# keypad.net
KiCad netlist of a schematic drawn in EAGLE
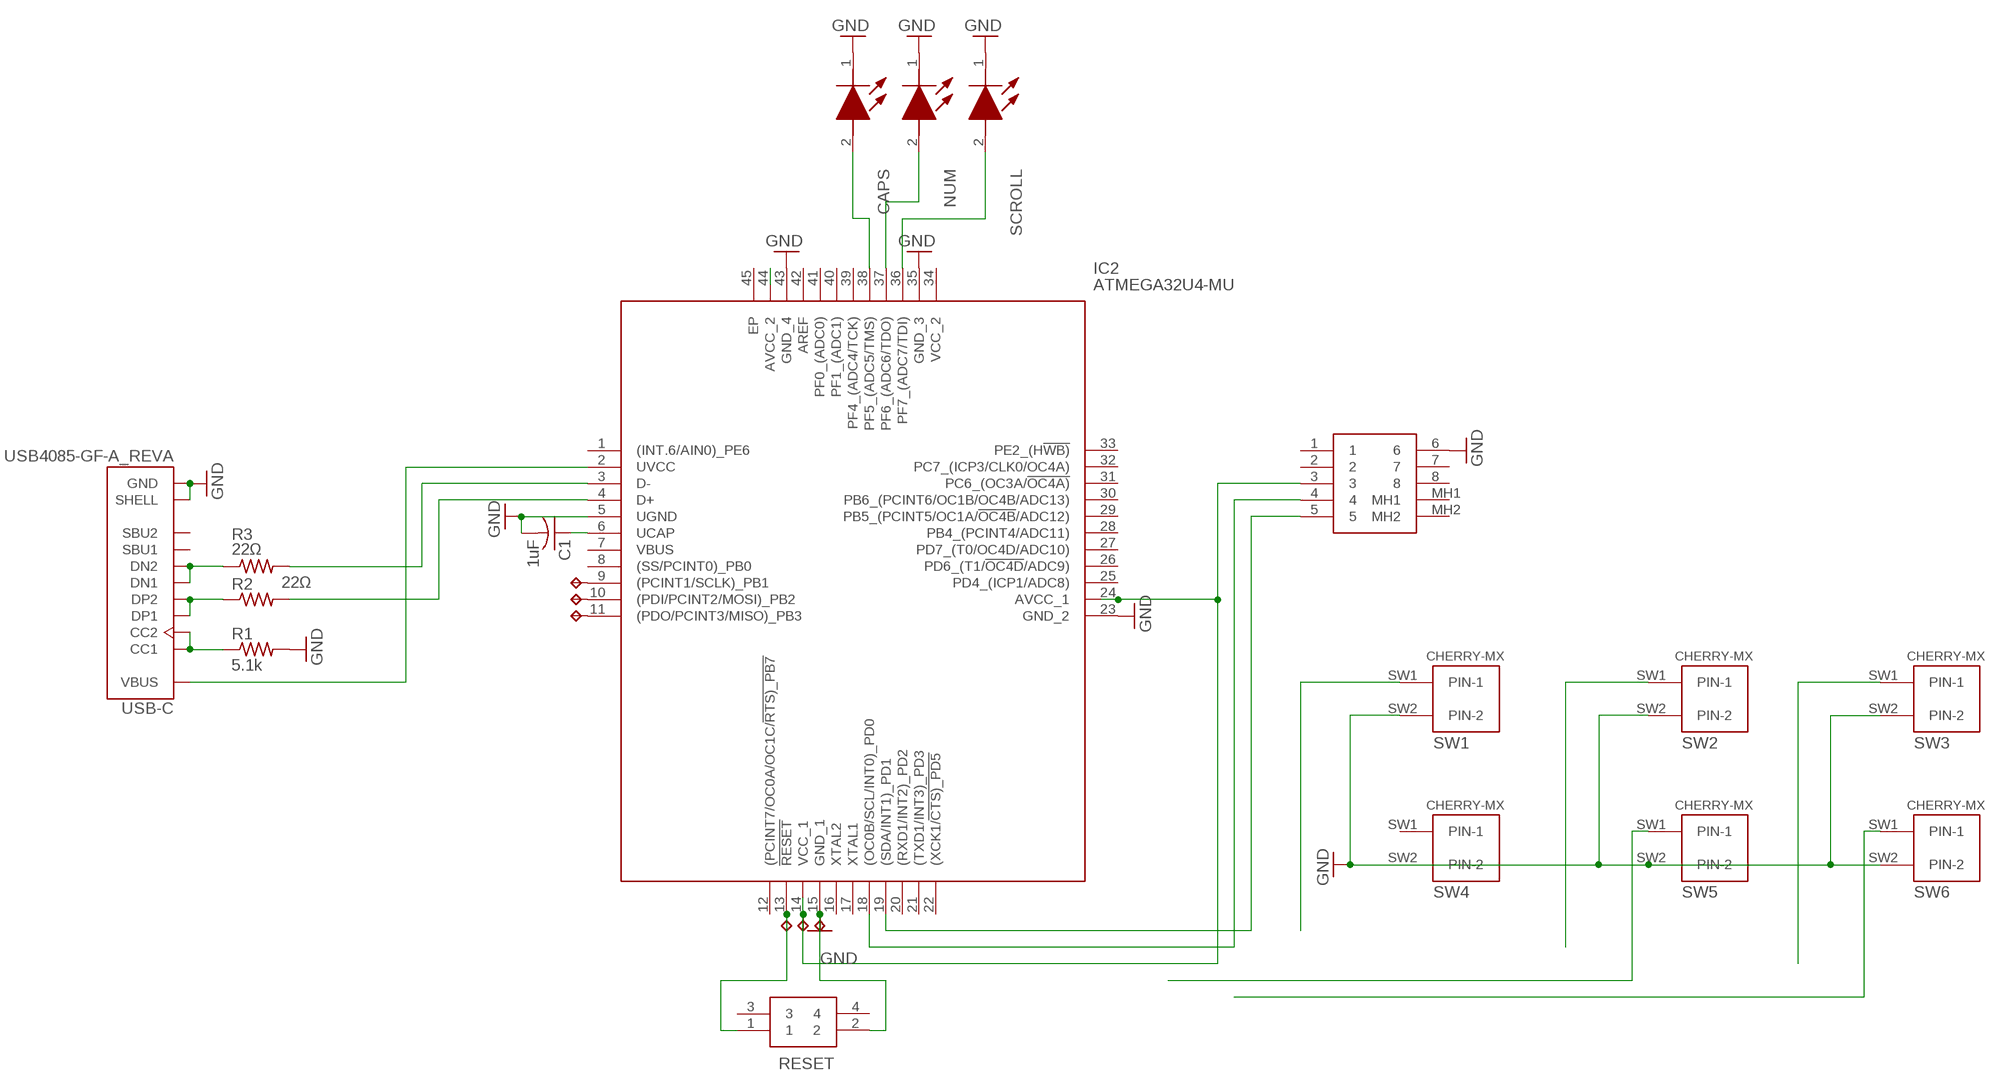
[diagram p0: schematic, sheet 1]

(export (version "E")
  (design (tool "Eeschema 10.0.6"))
  (components
    (comp (ref "5V")
      (value "TPTP17R")
      (footprint "eagle-import:TP17R")
      (libsource (lib "eagle-import") (part "TPTP17R"))
    )
    (comp (ref "C1")
      (value "1uF")
      (footprint "eagle-import:C0805")
      (libsource (lib "eagle-import") (part "C-USC0805"))
    )
    (comp (ref "CAPS")
      (value "155060GS75300")
      (footprint "eagle-import:155060GS75300")
      (fields (field (name "MOUSER_PART_NUMBER") "710-155060GS75300"))
      (libsource (lib "eagle-import") (part "155060GS75300"))
    )
    (comp (ref "GND")
      (value "TPTP17R")
      (footprint "eagle-import:TP17R")
      (libsource (lib "eagle-import") (part "TPTP17R"))
    )
    (comp (ref "IC2")
      (value "ATMEGA32U4-MU")
      (footprint "eagle-import:QFN50P700X700X100-45N")
      (fields (field (name "MOUSER_PART_NUMBER") "556-ATMEGA32U4-MU"))
      (libsource (lib "eagle-import") (part "ATMEGA32U4-MU"))
    )
    (comp (ref "J2")
      (value "SS-60300-046")
      (footprint "eagle-import:SS60300046")
      (fields (field (name "MOUSER_PART_NUMBER") "530-SS-60300-046"))
      (libsource (lib "eagle-import") (part "SS-60300-046"))
    )
    (comp (ref "MISO")
      (value "TPTP17R")
      (footprint "eagle-import:TP17R")
      (libsource (lib "eagle-import") (part "TPTP17R"))
    )
    (comp (ref "MOSI")
      (value "TPTP17R")
      (footprint "eagle-import:TP17R")
      (libsource (lib "eagle-import") (part "TPTP17R"))
    )
    (comp (ref "NUM")
      (value "155060GS75300")
      (footprint "eagle-import:155060GS75300")
      (fields (field (name "MOUSER_PART_NUMBER") "710-155060GS75300"))
      (libsource (lib "eagle-import") (part "155060GS75300"))
    )
    (comp (ref "R1")
      (value "5.1k")
      (footprint "eagle-import:R0603")
      (libsource (lib "eagle-import") (part "R-US_R0603"))
    )
    (comp (ref "R2")
      (value "22Ω")
      (footprint "eagle-import:R0805")
      (libsource (lib "eagle-import") (part "R-US_R0805"))
    )
    (comp (ref "R3")
      (value "22Ω")
      (footprint "eagle-import:R0805")
      (libsource (lib "eagle-import") (part "R-US_R0805"))
    )
    (comp (ref "RESET")
      (value "LL3303F065QG")
      (footprint "eagle-import:LL3303F065QG")
      (fields (field (name "MOUSER_PART_NUMBER") "612-LL3303F065QG"))
      (libsource (lib "eagle-import") (part "LL3303F065QG"))
    )
    (comp (ref "RST")
      (value "TPTP17R")
      (footprint "eagle-import:TP17R")
      (libsource (lib "eagle-import") (part "TPTP17R"))
    )
    (comp (ref "SCLK")
      (value "TPTP17R")
      (footprint "eagle-import:TP17R")
      (libsource (lib "eagle-import") (part "TPTP17R"))
    )
    (comp (ref "SCROLL")
      (value "155060GS75300")
      (footprint "eagle-import:155060GS75300")
      (fields (field (name "MOUSER_PART_NUMBER") "710-155060GS75300"))
      (libsource (lib "eagle-import") (part "155060GS75300"))
    )
    (comp (ref "SW1")
      (value "CHERRY-MX")
      (footprint "eagle-import:CHERRY-MX")
      (libsource (lib "eagle-import") (part "CHERRY-MX"))
    )
    (comp (ref "SW2")
      (value "CHERRY-MX")
      (footprint "eagle-import:CHERRY-MX")
      (libsource (lib "eagle-import") (part "CHERRY-MX"))
    )
    (comp (ref "SW3")
      (value "CHERRY-MX")
      (footprint "eagle-import:CHERRY-MX")
      (libsource (lib "eagle-import") (part "CHERRY-MX"))
    )
    (comp (ref "SW4")
      (value "CHERRY-MX")
      (footprint "eagle-import:CHERRY-MX")
      (libsource (lib "eagle-import") (part "CHERRY-MX"))
    )
    (comp (ref "SW5")
      (value "CHERRY-MX")
      (footprint "eagle-import:CHERRY-MX")
      (libsource (lib "eagle-import") (part "CHERRY-MX"))
    )
    (comp (ref "SW6")
      (value "CHERRY-MX")
      (footprint "eagle-import:CHERRY-MX")
      (libsource (lib "eagle-import") (part "CHERRY-MX"))
    )
    (comp (ref "USB-C")
      (value "USB4085-GF-A_REVA")
      (footprint "eagle-import:GCT_USB4085-GF-A_REVA")
      (fields (field (name "MF") "Global Connector Technology") (field (name "MP") "USB4085-GF-A"))
      (libsource (lib "eagle-import") (part "USB4085-GF-A_REVA"))
    )
  )
  (nets
    (net (code "1") (name "/VCC") (class "Default")
      (node (ref "5V") (pin "TP") (pinfunction "TP_TP") (pintype "input"))
      (node (ref "IC2") (pin "14") (pinfunction "VCC_1_14") (pintype "bidirectional"))
      (node (ref "IC2") (pin "24") (pinfunction "AVCC_1_24") (pintype "bidirectional"))
      (node (ref "IC2") (pin "44") (pinfunction "AVCC_2_44") (pintype "bidirectional"))
      (node (ref "J2") (pin "3") (pinfunction "3_3") (pintype "bidirectional"))
    )
    (net (code "2") (name "GND") (class "Default")
      (node (ref "C1") (pin "2") (pinfunction "2_2") (pintype "passive"))
      (node (ref "CAPS") (pin "1") (pinfunction "K_1") (pintype "bidirectional"))
      (node (ref "GND") (pin "TP") (pinfunction "TP_TP") (pintype "input"))
      (node (ref "IC2") (pin "15") (pinfunction "GND_1_15") (pintype "bidirectional"))
      (node (ref "IC2") (pin "23") (pinfunction "GND_2_23") (pintype "bidirectional"))
      (node (ref "IC2") (pin "35") (pinfunction "GND_3_35") (pintype "bidirectional"))
      (node (ref "IC2") (pin "43") (pinfunction "GND_4_43") (pintype "bidirectional"))
      (node (ref "IC2") (pin "5") (pinfunction "UGND_5") (pintype "bidirectional"))
      (node (ref "J2") (pin "6") (pinfunction "6_6") (pintype "bidirectional"))
      (node (ref "NUM") (pin "1") (pinfunction "K_1") (pintype "bidirectional"))
      (node (ref "R1") (pin "2") (pinfunction "2_2") (pintype "passive"))
      (node (ref "RESET") (pin "2") (pinfunction "2_2") (pintype "bidirectional"))
      (node (ref "SCROLL") (pin "1") (pinfunction "K_1") (pintype "bidirectional"))
      (node (ref "SW1") (pin "SW2") (pinfunction "PIN-2_SW2") (pintype "bidirectional"))
      (node (ref "SW2") (pin "SW2") (pinfunction "PIN-2_SW2") (pintype "bidirectional"))
      (node (ref "SW3") (pin "SW2") (pinfunction "PIN-2_SW2") (pintype "bidirectional"))
      (node (ref "SW4") (pin "SW2") (pinfunction "PIN-2_SW2") (pintype "bidirectional"))
      (node (ref "SW5") (pin "SW2") (pinfunction "PIN-2_SW2") (pintype "bidirectional"))
      (node (ref "SW6") (pin "SW2") (pinfunction "PIN-2_SW2") (pintype "bidirectional"))
      (node (ref "USB-C") (pin "A1") (pinfunction "GND_A1") (pintype "passive"))
      (node (ref "USB-C") (pin "A12") (pinfunction "GND_A12") (pintype "passive"))
      (node (ref "USB-C") (pin "B1") (pinfunction "GND_B1") (pintype "passive"))
      (node (ref "USB-C") (pin "B12") (pinfunction "GND_B12") (pintype "passive"))
      (node (ref "USB-C") (pin "P1") (pinfunction "SHELL_P1") (pintype "passive"))
      (node (ref "USB-C") (pin "P2") (pinfunction "SHELL_P2") (pintype "passive"))
      (node (ref "USB-C") (pin "P3") (pinfunction "SHELL_P3") (pintype "passive"))
      (node (ref "USB-C") (pin "P4") (pinfunction "SHELL_P4") (pintype "passive"))
    )
    (net (code "3") (name "Net-(CAPS-A)") (class "Default")
      (node (ref "CAPS") (pin "2") (pinfunction "A_2") (pintype "bidirectional"))
      (node (ref "IC2") (pin "38") (pinfunction "PF5_(ADC5/TMS)_38") (pintype "bidirectional"))
    )
    (net (code "4") (name "Net-(IC2-(OC0B{slash}SCL{slash}INT0)_PD0)") (class "Default")
      (node (ref "IC2") (pin "18") (pinfunction "(OC0B/SCL/INT0)_PD0_18") (pintype "bidirectional"))
      (node (ref "J2") (pin "4") (pinfunction "4_4") (pintype "bidirectional"))
    )
    (net (code "5") (name "Net-(IC2-(PCINT1{slash}SCLK)_PB1)") (class "Default")
      (node (ref "IC2") (pin "9") (pinfunction "(PCINT1/SCLK)_PB1_9") (pintype "bidirectional"))
      (node (ref "SCLK") (pin "TP") (pinfunction "TP_TP") (pintype "input"))
    )
    (net (code "6") (name "Net-(IC2-(PDI{slash}PCINT2{slash}MOSI)_PB2)") (class "Default")
      (node (ref "IC2") (pin "10") (pinfunction "(PDI/PCINT2/MOSI)_PB2_10") (pintype "bidirectional"))
      (node (ref "MOSI") (pin "TP") (pinfunction "TP_TP") (pintype "input"))
    )
    (net (code "7") (name "Net-(IC2-(PDO{slash}PCINT3{slash}MISO)_PB3)") (class "Default")
      (node (ref "IC2") (pin "11") (pinfunction "(PDO/PCINT3/MISO)_PB3_11") (pintype "bidirectional"))
      (node (ref "MISO") (pin "TP") (pinfunction "TP_TP") (pintype "input"))
    )
    (net (code "8") (name "Net-(IC2-(SDA{slash}INT1)_PD1)") (class "Default")
      (node (ref "IC2") (pin "19") (pinfunction "(SDA/INT1)_PD1_19") (pintype "bidirectional"))
      (node (ref "J2") (pin "5") (pinfunction "5_5") (pintype "bidirectional"))
    )
    (net (code "9") (name "Net-(IC2-D+)") (class "Default")
      (node (ref "IC2") (pin "4") (pinfunction "D+_4") (pintype "bidirectional"))
      (node (ref "R2") (pin "2") (pinfunction "2_2") (pintype "passive"))
    )
    (net (code "10") (name "Net-(IC2-D-)") (class "Default")
      (node (ref "IC2") (pin "3") (pinfunction "D-_3") (pintype "bidirectional"))
      (node (ref "R3") (pin "2") (pinfunction "2_2") (pintype "passive"))
    )
    (net (code "11") (name "Net-(IC2-PF6_(ADC6{slash}TDO))") (class "Default")
      (node (ref "IC2") (pin "37") (pinfunction "PF6_(ADC6/TDO)_37") (pintype "bidirectional"))
      (node (ref "NUM") (pin "2") (pinfunction "A_2") (pintype "bidirectional"))
    )
    (net (code "12") (name "Net-(IC2-PF7_(ADC7{slash}TDI))") (class "Default")
      (node (ref "IC2") (pin "36") (pinfunction "PF7_(ADC7/TDI)_36") (pintype "bidirectional"))
      (node (ref "SCROLL") (pin "2") (pinfunction "A_2") (pintype "bidirectional"))
    )
    (net (code "13") (name "Net-(IC2-UCAP)") (class "Default")
      (node (ref "C1") (pin "1") (pinfunction "1_1") (pintype "passive"))
      (node (ref "IC2") (pin "6") (pinfunction "UCAP_6") (pintype "bidirectional"))
    )
    (net (code "14") (name "Net-(IC2-UVCC)") (class "Default")
      (node (ref "IC2") (pin "2") (pinfunction "UVCC_2") (pintype "bidirectional"))
      (node (ref "USB-C") (pin "A4") (pinfunction "VBUS_A4") (pintype "power_in"))
      (node (ref "USB-C") (pin "A9") (pinfunction "VBUS_A9") (pintype "power_in"))
      (node (ref "USB-C") (pin "B4") (pinfunction "VBUS_B4") (pintype "power_in"))
      (node (ref "USB-C") (pin "B9") (pinfunction "VBUS_B9") (pintype "power_in"))
    )
    (net (code "15") (name "Net-(IC2-~{RESET})") (class "Default")
      (node (ref "IC2") (pin "13") (pinfunction "~{RESET}_13") (pintype "bidirectional"))
      (node (ref "RESET") (pin "1") (pinfunction "1_1") (pintype "bidirectional"))
      (node (ref "RST") (pin "TP") (pinfunction "TP_TP") (pintype "input"))
    )
    (net (code "16") (name "Net-(USB-C-CC1)") (class "Default")
      (node (ref "R1") (pin "1") (pinfunction "1_1") (pintype "passive"))
      (node (ref "USB-C") (pin "A5") (pinfunction "CC1_A5") (pintype "bidirectional"))
      (node (ref "USB-C") (pin "B5") (pinfunction "CC2_B5") (pintype "bidirectional"))
    )
    (net (code "17") (name "Net-(USB-C-DN1)") (class "Default")
      (node (ref "R3") (pin "1") (pinfunction "1_1") (pintype "passive"))
      (node (ref "USB-C") (pin "A7") (pinfunction "DN1_A7") (pintype "bidirectional"))
      (node (ref "USB-C") (pin "B7") (pinfunction "DN2_B7") (pintype "bidirectional"))
    )
    (net (code "18") (name "Net-(USB-C-DP1)") (class "Default")
      (node (ref "R2") (pin "1") (pinfunction "1_1") (pintype "passive"))
      (node (ref "USB-C") (pin "A6") (pinfunction "DP1_A6") (pintype "bidirectional"))
      (node (ref "USB-C") (pin "B6") (pinfunction "DP2_B6") (pintype "bidirectional"))
    )
    (net (code "19") (name "unconnected-(IC2-(INT.6{slash}AIN0)_PE6-Pad1)") (class "Default")
      (node (ref "IC2") (pin "1") (pinfunction "(INT.6/AIN0)_PE6_1") (pintype "bidirectional"))
    )
    (net (code "20") (name "unconnected-(IC2-(PCINT7{slash}OC0A{slash}OC1C{slash}~{RTS})_PB7-Pad12)") (class "Default")
      (node (ref "IC2") (pin "12") (pinfunction "(PCINT7/OC0A/OC1C/~{RTS})_PB7_12") (pintype "bidirectional"))
    )
    (net (code "21") (name "unconnected-(IC2-(RXD1{slash}INT2)_PD2-Pad20)") (class "Default")
      (node (ref "IC2") (pin "20") (pinfunction "(RXD1/INT2)_PD2_20") (pintype "bidirectional"))
    )
    (net (code "22") (name "unconnected-(IC2-(SS{slash}PCINT0)_PB0-Pad8)") (class "Default")
      (node (ref "IC2") (pin "8") (pinfunction "(SS/PCINT0)_PB0_8") (pintype "bidirectional"))
    )
    (net (code "23") (name "unconnected-(IC2-(TXD1{slash}INT3)_PD3-Pad21)") (class "Default")
      (node (ref "IC2") (pin "21") (pinfunction "(TXD1/INT3)_PD3_21") (pintype "bidirectional"))
    )
    (net (code "24") (name "unconnected-(IC2-(XCK1{slash}~{CTS})_PD5-Pad22)") (class "Default")
      (node (ref "IC2") (pin "22") (pinfunction "(XCK1/~{CTS})_PD5_22") (pintype "bidirectional"))
    )
    (net (code "25") (name "unconnected-(IC2-AREF-Pad42)") (class "Default")
      (node (ref "IC2") (pin "42") (pinfunction "AREF_42") (pintype "bidirectional"))
    )
    (net (code "26") (name "unconnected-(IC2-EP-Pad45)") (class "Default")
      (node (ref "IC2") (pin "45") (pinfunction "EP_45") (pintype "bidirectional"))
    )
    (net (code "27") (name "unconnected-(IC2-PB4_(PCINT4{slash}ADC11)-Pad28)") (class "Default")
      (node (ref "IC2") (pin "28") (pinfunction "PB4_(PCINT4/ADC11)_28") (pintype "bidirectional"))
    )
    (net (code "28") (name "unconnected-(IC2-PB5_(PCINT5{slash}OC1A{slash}~{OC4B}{slash}ADC12)-Pad29)") (class "Default")
      (node (ref "IC2") (pin "29") (pinfunction "PB5_(PCINT5/OC1A/~{OC4B}/ADC12)_29") (pintype "bidirectional"))
    )
    (net (code "29") (name "unconnected-(IC2-PB6_(PCINT6{slash}OC1B{slash}OC4B{slash}ADC13)-Pad30)") (class "Default")
      (node (ref "IC2") (pin "30") (pinfunction "PB6_(PCINT6/OC1B/OC4B/ADC13)_30") (pintype "bidirectional"))
    )
    (net (code "30") (name "unconnected-(IC2-PC6_(OC3A{slash}~{OC4A})-Pad31)") (class "Default")
      (node (ref "IC2") (pin "31") (pinfunction "PC6_(OC3A/~{OC4A})_31") (pintype "bidirectional"))
    )
    (net (code "31") (name "unconnected-(IC2-PC7_(ICP3{slash}CLK0{slash}OC4A)-Pad32)") (class "Default")
      (node (ref "IC2") (pin "32") (pinfunction "PC7_(ICP3/CLK0/OC4A)_32") (pintype "bidirectional"))
    )
    (net (code "32") (name "unconnected-(IC2-PD4_(ICP1{slash}ADC8)-Pad25)") (class "Default")
      (node (ref "IC2") (pin "25") (pinfunction "PD4_(ICP1/ADC8)_25") (pintype "bidirectional"))
    )
    (net (code "33") (name "unconnected-(IC2-PD6_(T1{slash}~{OC4D}{slash}ADC9)-Pad26)") (class "Default")
      (node (ref "IC2") (pin "26") (pinfunction "PD6_(T1/~{OC4D}/ADC9)_26") (pintype "bidirectional"))
    )
    (net (code "34") (name "unconnected-(IC2-PD7_(T0{slash}OC4D{slash}ADC10)-Pad27)") (class "Default")
      (node (ref "IC2") (pin "27") (pinfunction "PD7_(T0/OC4D/ADC10)_27") (pintype "bidirectional"))
    )
    (net (code "35") (name "unconnected-(IC2-PE2_(H~{WB})-Pad33)") (class "Default")
      (node (ref "IC2") (pin "33") (pinfunction "PE2_(H~{WB})_33") (pintype "bidirectional"))
    )
    (net (code "36") (name "unconnected-(IC2-PF0_(ADC0)-Pad41)") (class "Default")
      (node (ref "IC2") (pin "41") (pinfunction "PF0_(ADC0)_41") (pintype "bidirectional"))
    )
    (net (code "37") (name "unconnected-(IC2-PF1_(ADC1)-Pad40)") (class "Default")
      (node (ref "IC2") (pin "40") (pinfunction "PF1_(ADC1)_40") (pintype "bidirectional"))
    )
    (net (code "38") (name "unconnected-(IC2-PF4_(ADC4{slash}TCK)-Pad39)") (class "Default")
      (node (ref "IC2") (pin "39") (pinfunction "PF4_(ADC4/TCK)_39") (pintype "bidirectional"))
    )
    (net (code "39") (name "unconnected-(IC2-VBUS-Pad7)") (class "Default")
      (node (ref "IC2") (pin "7") (pinfunction "VBUS_7") (pintype "bidirectional"))
    )
    (net (code "40") (name "unconnected-(IC2-VCC_2-Pad34)") (class "Default")
      (node (ref "IC2") (pin "34") (pinfunction "VCC_2_34") (pintype "bidirectional"))
    )
    (net (code "41") (name "unconnected-(IC2-XTAL1-Pad17)") (class "Default")
      (node (ref "IC2") (pin "17") (pinfunction "XTAL1_17") (pintype "bidirectional"))
    )
    (net (code "42") (name "unconnected-(IC2-XTAL2-Pad16)") (class "Default")
      (node (ref "IC2") (pin "16") (pinfunction "XTAL2_16") (pintype "bidirectional"))
    )
    (net (code "43") (name "unconnected-(J2-Pad1)") (class "Default")
      (node (ref "J2") (pin "1") (pinfunction "1_1") (pintype "bidirectional"))
    )
    (net (code "44") (name "unconnected-(J2-Pad2)") (class "Default")
      (node (ref "J2") (pin "2") (pinfunction "2_2") (pintype "bidirectional"))
    )
    (net (code "45") (name "unconnected-(J2-Pad7)") (class "Default")
      (node (ref "J2") (pin "7") (pinfunction "7_7") (pintype "bidirectional"))
    )
    (net (code "46") (name "unconnected-(J2-Pad8)") (class "Default")
      (node (ref "J2") (pin "8") (pinfunction "8_8") (pintype "bidirectional"))
    )
    (net (code "47") (name "unconnected-(J2-PadMH1)") (class "Default")
      (node (ref "J2") (pin "MH1") (pinfunction "MH1_MH1") (pintype "bidirectional"))
    )
    (net (code "48") (name "unconnected-(J2-PadMH2)") (class "Default")
      (node (ref "J2") (pin "MH2") (pinfunction "MH2_MH2") (pintype "bidirectional"))
    )
    (net (code "49") (name "unconnected-(RESET-Pad3)") (class "Default")
      (node (ref "RESET") (pin "3") (pinfunction "3_3") (pintype "bidirectional"))
    )
    (net (code "50") (name "unconnected-(RESET-Pad4)") (class "Default")
      (node (ref "RESET") (pin "4") (pinfunction "4_4") (pintype "bidirectional"))
    )
    (net (code "51") (name "unconnected-(SW1-PIN-1-PadSW1)") (class "Default")
      (node (ref "SW1") (pin "SW1") (pinfunction "PIN-1_SW1") (pintype "bidirectional"))
    )
    (net (code "52") (name "unconnected-(SW2-PIN-1-PadSW1)") (class "Default")
      (node (ref "SW2") (pin "SW1") (pinfunction "PIN-1_SW1") (pintype "bidirectional"))
    )
    (net (code "53") (name "unconnected-(SW3-PIN-1-PadSW1)") (class "Default")
      (node (ref "SW3") (pin "SW1") (pinfunction "PIN-1_SW1") (pintype "bidirectional"))
    )
    (net (code "54") (name "unconnected-(SW4-PIN-1-PadSW1)") (class "Default")
      (node (ref "SW4") (pin "SW1") (pinfunction "PIN-1_SW1") (pintype "bidirectional"))
    )
    (net (code "55") (name "unconnected-(SW5-PIN-1-PadSW1)") (class "Default")
      (node (ref "SW5") (pin "SW1") (pinfunction "PIN-1_SW1") (pintype "bidirectional"))
    )
    (net (code "56") (name "unconnected-(SW6-PIN-1-PadSW1)") (class "Default")
      (node (ref "SW6") (pin "SW1") (pinfunction "PIN-1_SW1") (pintype "bidirectional"))
    )
    (net (code "57") (name "unconnected-(USB-C-SBU1-PadA8)") (class "Default")
      (node (ref "USB-C") (pin "A8") (pinfunction "SBU1_A8") (pintype "bidirectional"))
    )
    (net (code "58") (name "unconnected-(USB-C-SBU2-PadB8)") (class "Default")
      (node (ref "USB-C") (pin "B8") (pinfunction "SBU2_B8") (pintype "bidirectional"))
    )
  )
)
